# Right_Bar.net
KiCad netlist of a schematic drawn in EAGLE
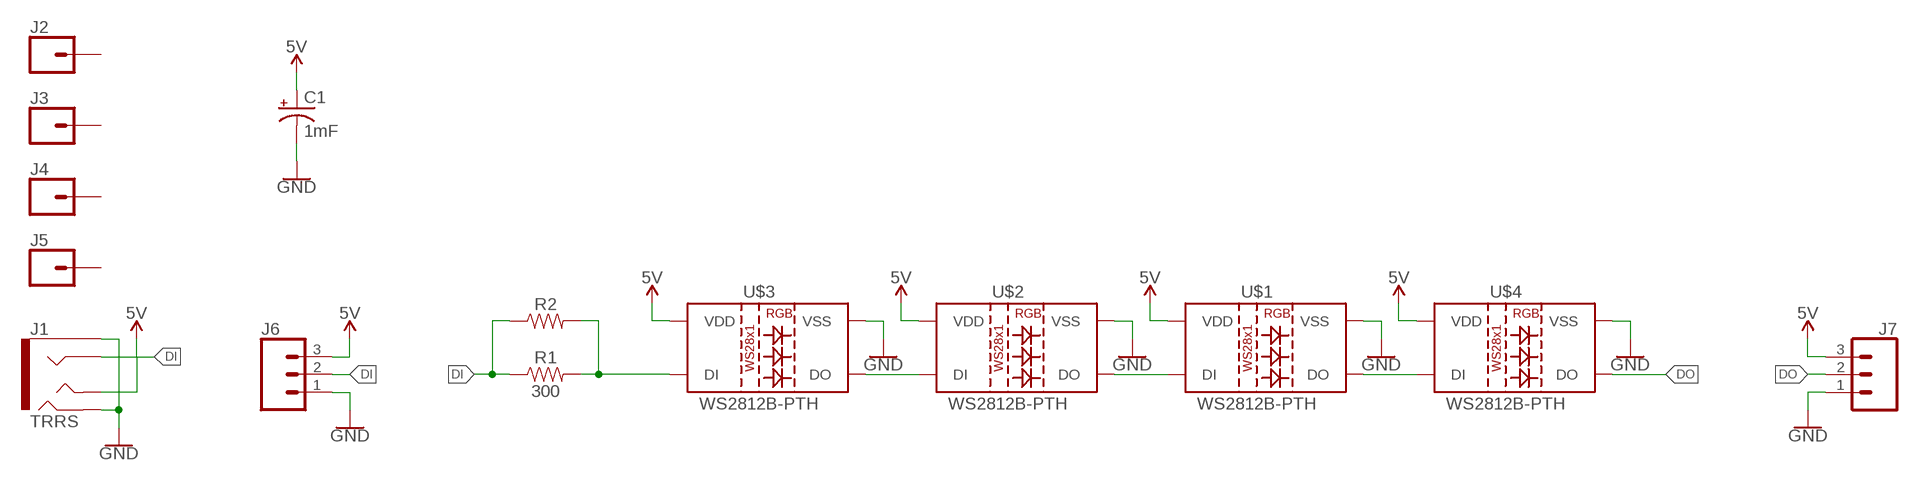
[diagram p0: schematic, sheet 1]

(export (version "E")
  (design (tool "Eeschema 10.0.6"))
  (components
    (comp (ref "C1")
      (value "1mF")
      (footprint "eagle-import:CPOL-RADIAL-5MM-10MM")
      (libsource (lib "eagle-import") (part "1000UF-RADIAL-5MM-25V-20%"))
    )
    (comp (ref "J1")
      (value "TRRS")
      (footprint "eagle-import:AUDIO_JACK_3.5MM_TRRS_SMD_RA")
      (libsource (lib "eagle-import") (part "AUDIO_JACK_TRRSSMD_RA"))
    )
    (comp (ref "J2")
      (value "CONN_01OFFSET")
      (footprint "eagle-import:1X01_OFFSET")
      (libsource (lib "eagle-import") (part "CONN_01OFFSET"))
    )
    (comp (ref "J3")
      (value "CONN_01OFFSET")
      (footprint "eagle-import:1X01_OFFSET")
      (libsource (lib "eagle-import") (part "CONN_01OFFSET"))
    )
    (comp (ref "J4")
      (value "CONN_01OFFSET")
      (footprint "eagle-import:1X01_OFFSET")
      (libsource (lib "eagle-import") (part "CONN_01OFFSET"))
    )
    (comp (ref "J5")
      (value "CONN_01OFFSET")
      (footprint "eagle-import:1X01_OFFSET")
      (libsource (lib "eagle-import") (part "CONN_01OFFSET"))
    )
    (comp (ref "J6")
      (value "CONN_03")
      (footprint "eagle-import:1X03")
      (libsource (lib "eagle-import") (part "CONN_03"))
    )
    (comp (ref "J7")
      (value "CONN_03")
      (footprint "eagle-import:1X03")
      (libsource (lib "eagle-import") (part "CONN_03"))
    )
    (comp (ref "R1")
      (value "300")
      (footprint "eagle-import:0603")
      (libsource (lib "eagle-import") (part "300OHM-0603-1/10W-1%"))
    )
    (comp (ref "R2")
      (value "RESISTORAXIAL-0.3")
      (footprint "eagle-import:AXIAL-0.3")
      (libsource (lib "eagle-import") (part "RESISTORAXIAL-0.3"))
    )
    (comp (ref "U$1")
      (value "WS2812B-PTH")
      (footprint "eagle-import:WS2812B-PTH-KIT")
      (libsource (lib "eagle-import") (part "WS2812B-PTH"))
    )
    (comp (ref "U$2")
      (value "WS2812B-PTH")
      (footprint "eagle-import:WS2812B-PTH-KIT")
      (libsource (lib "eagle-import") (part "WS2812B-PTH"))
    )
    (comp (ref "U$3")
      (value "WS2812B-PTH")
      (footprint "eagle-import:WS2812B-PTH-KIT")
      (libsource (lib "eagle-import") (part "WS2812B-PTH"))
    )
    (comp (ref "U$4")
      (value "WS2812B-PTH")
      (footprint "eagle-import:WS2812B-PTH-KIT")
      (libsource (lib "eagle-import") (part "WS2812B-PTH"))
    )
  )
  (nets
    (net (code "1") (name "5V") (class "Default")
      (node (ref "C1") (pin "+") (pinfunction "+_+") (pintype "passive"))
      (node (ref "J1") (pin "TIP") (pinfunction "TIP_TIP") (pintype "bidirectional"))
      (node (ref "J6") (pin "3") (pinfunction "3_3") (pintype "passive"))
      (node (ref "J7") (pin "3") (pinfunction "3_3") (pintype "passive"))
      (node (ref "U$1") (pin "2") (pinfunction "VDD_2") (pintype "bidirectional"))
      (node (ref "U$2") (pin "2") (pinfunction "VDD_2") (pintype "bidirectional"))
      (node (ref "U$3") (pin "2") (pinfunction "VDD_2") (pintype "bidirectional"))
      (node (ref "U$4") (pin "2") (pinfunction "VDD_2") (pintype "bidirectional"))
    )
    (net (code "2") (name "DI") (class "Default")
      (node (ref "J1") (pin "RING1") (pinfunction "RING1_RING1") (pintype "bidirectional"))
      (node (ref "J6") (pin "2") (pinfunction "2_2") (pintype "passive"))
      (node (ref "R1") (pin "1") (pinfunction "1_1") (pintype "passive"))
      (node (ref "R2") (pin "P$1") (pinfunction "1_P$1") (pintype "passive"))
    )
    (net (code "3") (name "DO") (class "Default")
      (node (ref "J7") (pin "2") (pinfunction "2_2") (pintype "passive"))
      (node (ref "U$4") (pin "4") (pinfunction "DO_4") (pintype "bidirectional"))
    )
    (net (code "4") (name "GND") (class "Default")
      (node (ref "C1") (pin "-") (pinfunction "-_-") (pintype "passive"))
      (node (ref "J1") (pin "EARTH") (pinfunction "EARTH_EARTH") (pintype "bidirectional"))
      (node (ref "J1") (pin "RING2") (pinfunction "RING2_RING2") (pintype "bidirectional"))
      (node (ref "J6") (pin "1") (pinfunction "1_1") (pintype "passive"))
      (node (ref "J7") (pin "1") (pinfunction "1_1") (pintype "passive"))
      (node (ref "U$1") (pin "3") (pinfunction "VSS_3") (pintype "bidirectional"))
      (node (ref "U$2") (pin "3") (pinfunction "VSS_3") (pintype "bidirectional"))
      (node (ref "U$3") (pin "3") (pinfunction "VSS_3") (pintype "bidirectional"))
      (node (ref "U$4") (pin "3") (pinfunction "VSS_3") (pintype "bidirectional"))
    )
    (net (code "5") (name "Net-(R2-2)") (class "Default")
      (node (ref "R1") (pin "2") (pinfunction "2_2") (pintype "passive"))
      (node (ref "R2") (pin "P$2") (pinfunction "2_P$2") (pintype "passive"))
      (node (ref "U$3") (pin "1") (pinfunction "DI_1") (pintype "bidirectional"))
    )
    (net (code "6") (name "Net-(U$1-DI)") (class "Default")
      (node (ref "U$1") (pin "1") (pinfunction "DI_1") (pintype "bidirectional"))
      (node (ref "U$2") (pin "4") (pinfunction "DO_4") (pintype "bidirectional"))
    )
    (net (code "7") (name "Net-(U$1-DO)") (class "Default")
      (node (ref "U$1") (pin "4") (pinfunction "DO_4") (pintype "bidirectional"))
      (node (ref "U$4") (pin "1") (pinfunction "DI_1") (pintype "bidirectional"))
    )
    (net (code "8") (name "Net-(U$2-DI)") (class "Default")
      (node (ref "U$2") (pin "1") (pinfunction "DI_1") (pintype "bidirectional"))
      (node (ref "U$3") (pin "4") (pinfunction "DO_4") (pintype "bidirectional"))
    )
    (net (code "9") (name "unconnected-(J2-Pad1)") (class "Default")
      (node (ref "J2") (pin "1") (pinfunction "1_1") (pintype "passive"))
    )
    (net (code "10") (name "unconnected-(J3-Pad1)") (class "Default")
      (node (ref "J3") (pin "1") (pinfunction "1_1") (pintype "passive"))
    )
    (net (code "11") (name "unconnected-(J4-Pad1)") (class "Default")
      (node (ref "J4") (pin "1") (pinfunction "1_1") (pintype "passive"))
    )
    (net (code "12") (name "unconnected-(J5-Pad1)") (class "Default")
      (node (ref "J5") (pin "1") (pinfunction "1_1") (pintype "passive"))
    )
  )
)
